# AN_MUX.net
KiCad netlist of a schematic drawn in Altium Designer
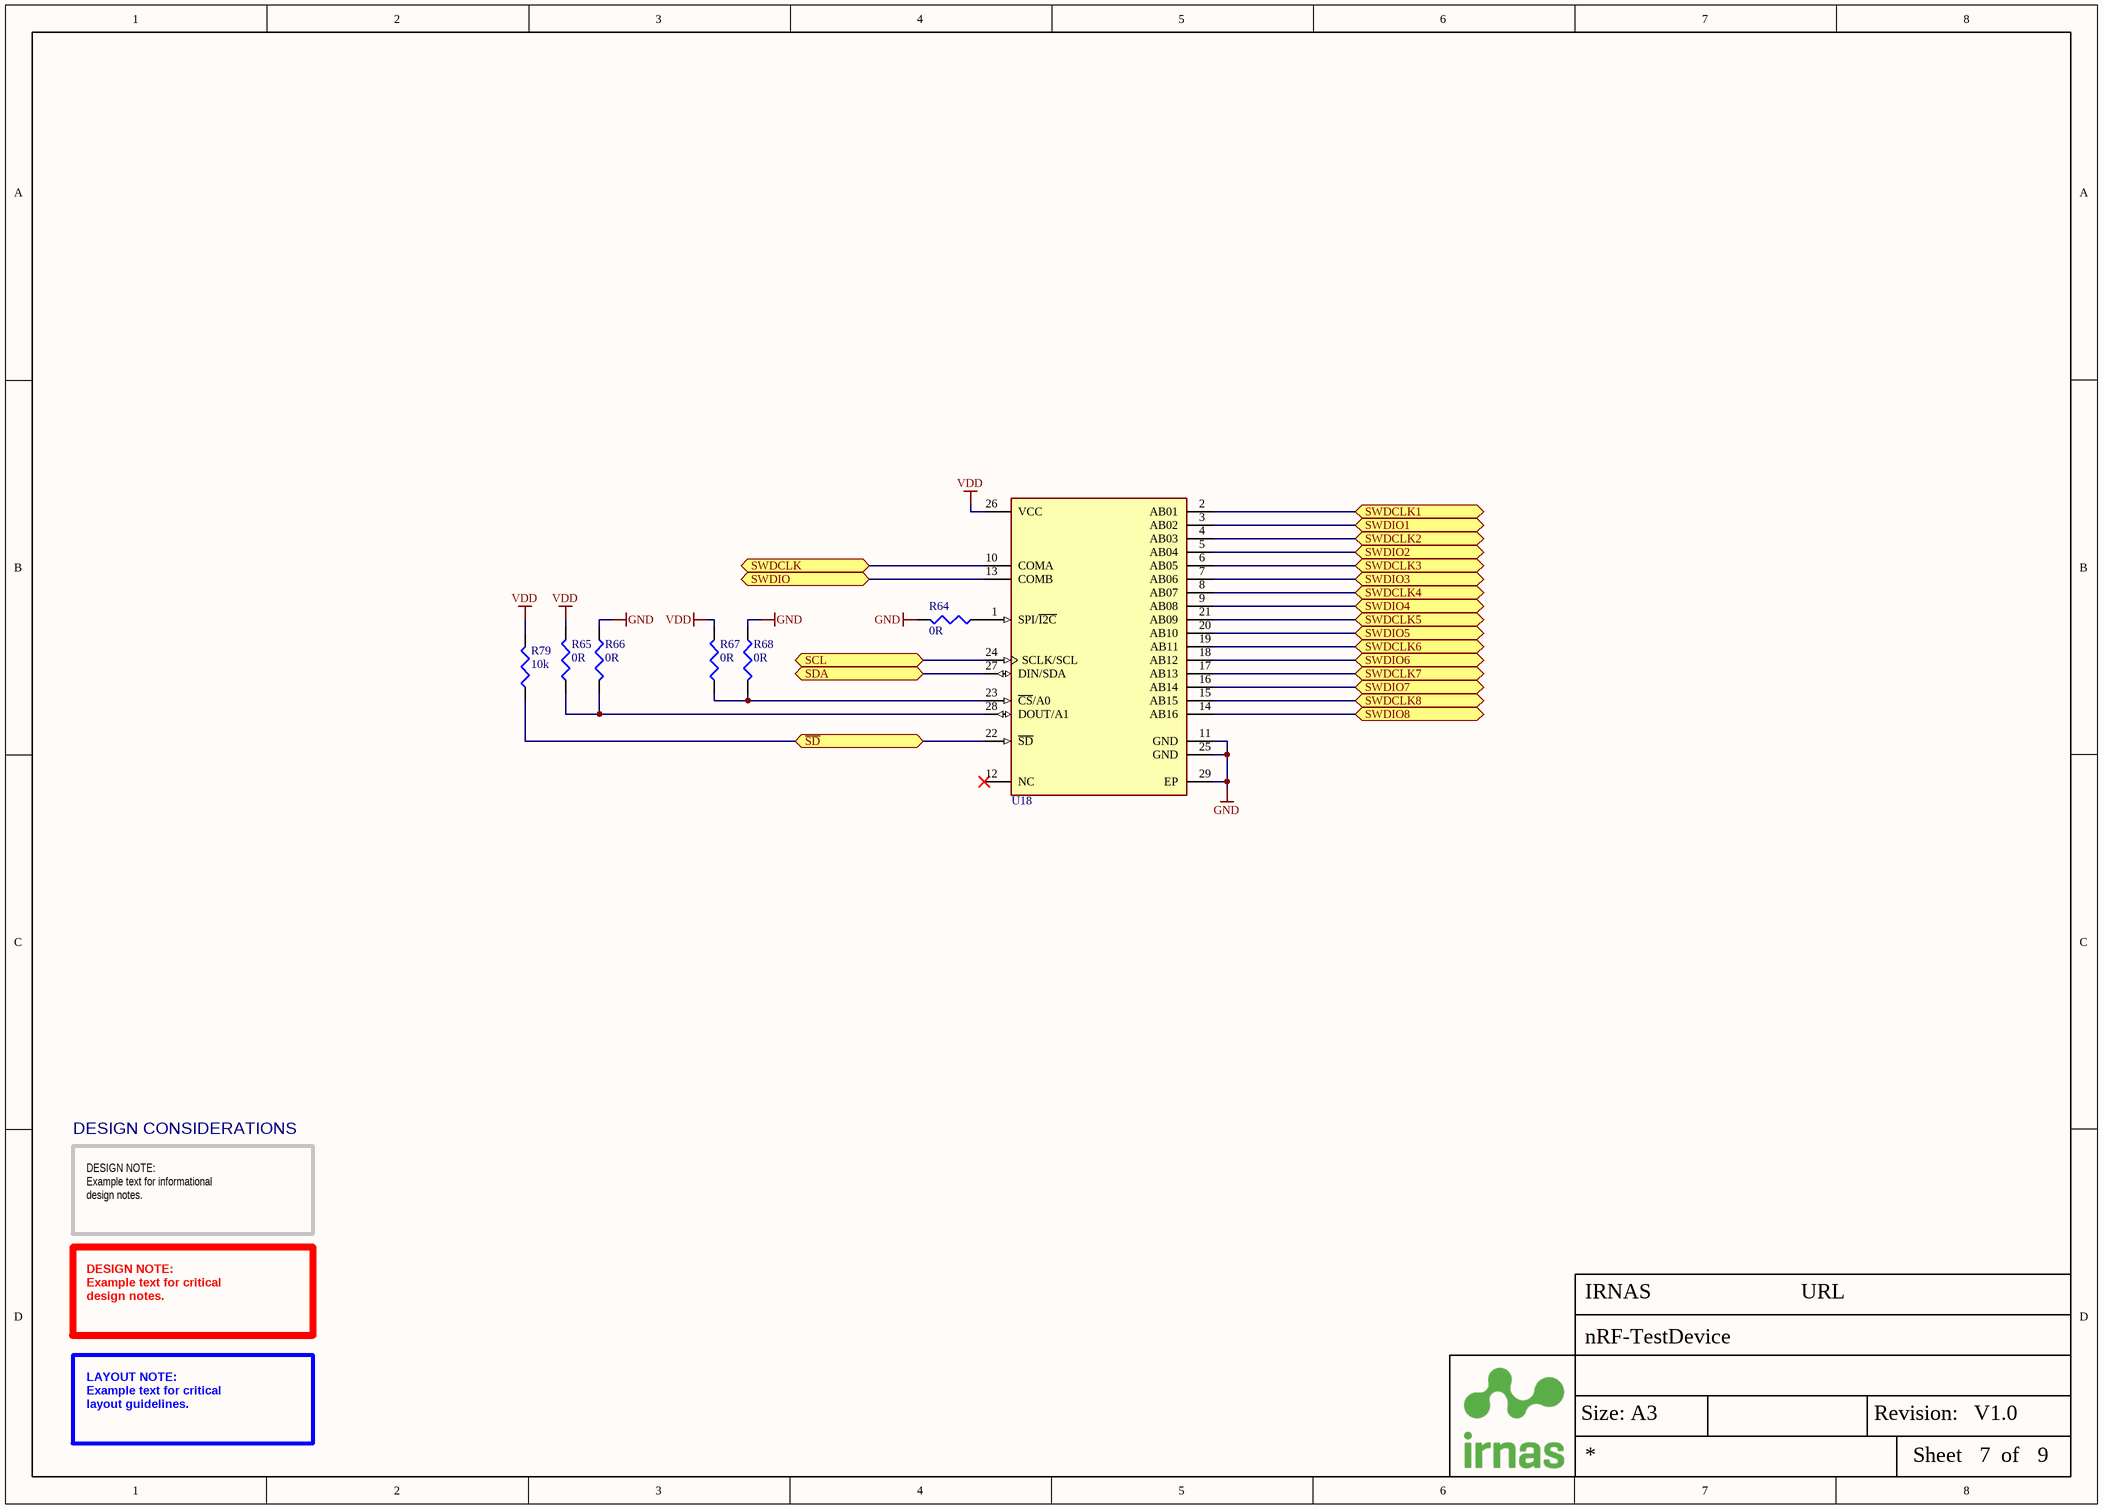
[diagram p0: AN_MUX.SchDoc]

(export (version "E")
  (design (tool "Eeschema 10.0.6"))
  (components
    (comp (ref "R64")
      (value "0R")
      (footprint "RES0402")
      (description "RESISTOR, 0402, 0R, ANTI SULFURATION")
      (fields
        (field (name "MANUFACTURER") "Multicomp")
        (field (name "MANUFACTURER PART NUMBER") "MCMR04X000PTL")
      )
      (libsource (lib "Passive") (part "R - 0R/0402"))
    )
    (comp (ref "R65")
      (value "0R")
      (footprint "RES0402")
      (description "RESISTOR, 0402, 0R, ANTI SULFURATION")
      (fields
        (field (name "MANUFACTURER") "Multicomp")
        (field (name "MANUFACTURER PART NUMBER") "MCMR04X000PTL")
      )
      (libsource (lib "Passive") (part "R - 0R/0402"))
    )
    (comp (ref "R66")
      (value "0R")
      (footprint "RES0402")
      (description "RESISTOR, 0402, 0R, ANTI SULFURATION")
      (fields
        (field (name "MANUFACTURER") "Multicomp")
        (field (name "MANUFACTURER PART NUMBER") "MCMR04X000PTL")
      )
      (libsource (lib "Passive") (part "R - 0R/0402"))
    )
    (comp (ref "R67")
      (value "0R")
      (footprint "RES0402")
      (description "RESISTOR, 0402, 0R, ANTI SULFURATION")
      (fields
        (field (name "MANUFACTURER") "Multicomp")
        (field (name "MANUFACTURER PART NUMBER") "MCMR04X000PTL")
      )
      (libsource (lib "Passive") (part "R - 0R/0402"))
    )
    (comp (ref "R68")
      (value "0R")
      (footprint "RES0402")
      (description "RESISTOR, 0402, 0R, ANTI SULFURATION")
      (fields
        (field (name "MANUFACTURER") "Multicomp")
        (field (name "MANUFACTURER PART NUMBER") "MCMR04X000PTL")
      )
      (libsource (lib "Passive") (part "R - 0R/0402"))
    )
    (comp (ref "R79")
      (value "10k")
      (footprint "RES0402")
      (fields
        (field (name "MANUFACTURER") "Multicomp")
        (field (name "MANUFACTURER PART NUMBER") "MCWR04X1002FTL")
        (field (name "TOLERANCE") "1%")
      )
      (libsource (lib "Passive") (part "R - 10k/0402"))
    )
    (comp (ref "U18")
      (value "INT - MAX14661ETI+")
      (footprint "Maxim_Integrated_T2844-1_IPC_A")
      (libsource (lib "Active") (part "INT - MAX14661ETI+"))
    )
  )
  (nets
    (net (code "1") (name "/SCL") (class "Default")
      (node (ref "U18") (pin "24") (pinfunction "SCLK/SCL_24") (pintype "input"))
    )
    (net (code "2") (name "/SDA") (class "Default")
      (node (ref "U18") (pin "27") (pinfunction "DIN/SDA_27") (pintype "bidirectional"))
    )
    (net (code "3") (name "/SWDCLK") (class "Default")
      (node (ref "U18") (pin "10") (pinfunction "COMA_10") (pintype "passive"))
    )
    (net (code "4") (name "/SWDCLK1") (class "Default")
      (node (ref "U18") (pin "2") (pinfunction "AB01_2") (pintype "passive"))
    )
    (net (code "5") (name "/SWDCLK2") (class "Default")
      (node (ref "U18") (pin "4") (pinfunction "AB03_4") (pintype "passive"))
    )
    (net (code "6") (name "/SWDCLK3") (class "Default")
      (node (ref "U18") (pin "6") (pinfunction "AB05_6") (pintype "passive"))
    )
    (net (code "7") (name "/SWDCLK4") (class "Default")
      (node (ref "U18") (pin "8") (pinfunction "AB07_8") (pintype "passive"))
    )
    (net (code "8") (name "/SWDCLK5") (class "Default")
      (node (ref "U18") (pin "21") (pinfunction "AB09_21") (pintype "passive"))
    )
    (net (code "9") (name "/SWDCLK6") (class "Default")
      (node (ref "U18") (pin "19") (pinfunction "AB11_19") (pintype "passive"))
    )
    (net (code "10") (name "/SWDCLK7") (class "Default")
      (node (ref "U18") (pin "17") (pinfunction "AB13_17") (pintype "passive"))
    )
    (net (code "11") (name "/SWDCLK8") (class "Default")
      (node (ref "U18") (pin "15") (pinfunction "AB15_15") (pintype "passive"))
    )
    (net (code "12") (name "/SWDIO") (class "Default")
      (node (ref "U18") (pin "13") (pinfunction "COMB_13") (pintype "passive"))
    )
    (net (code "13") (name "/SWDIO1") (class "Default")
      (node (ref "U18") (pin "3") (pinfunction "AB02_3") (pintype "passive"))
    )
    (net (code "14") (name "/SWDIO2") (class "Default")
      (node (ref "U18") (pin "5") (pinfunction "AB04_5") (pintype "passive"))
    )
    (net (code "15") (name "/SWDIO3") (class "Default")
      (node (ref "U18") (pin "7") (pinfunction "AB06_7") (pintype "passive"))
    )
    (net (code "16") (name "/SWDIO4") (class "Default")
      (node (ref "U18") (pin "9") (pinfunction "AB08_9") (pintype "passive"))
    )
    (net (code "17") (name "/SWDIO5") (class "Default")
      (node (ref "U18") (pin "20") (pinfunction "AB10_20") (pintype "passive"))
    )
    (net (code "18") (name "/SWDIO6") (class "Default")
      (node (ref "U18") (pin "18") (pinfunction "AB12_18") (pintype "passive"))
    )
    (net (code "19") (name "/SWDIO7") (class "Default")
      (node (ref "U18") (pin "16") (pinfunction "AB14_16") (pintype "passive"))
    )
    (net (code "20") (name "/SWDIO8") (class "Default")
      (node (ref "U18") (pin "14") (pinfunction "AB16_14") (pintype "passive"))
    )
    (net (code "21") (name "/~{SD}") (class "Default")
      (node (ref "R79") (pin "1") (pinfunction "1_1") (pintype "passive"))
      (node (ref "U18") (pin "22") (pinfunction "~{SD}_22") (pintype "input"))
    )
    (net (code "22") (name "GND") (class "Default")
      (node (ref "R64") (pin "2") (pinfunction "2_2") (pintype "passive"))
      (node (ref "R66") (pin "1") (pinfunction "1_1") (pintype "passive"))
      (node (ref "R68") (pin "1") (pinfunction "1_1") (pintype "passive"))
      (node (ref "U18") (pin "11") (pinfunction "GND_11") (pintype "passive"))
      (node (ref "U18") (pin "25") (pinfunction "GND_25") (pintype "passive"))
      (node (ref "U18") (pin "29") (pinfunction "EP_29") (pintype "passive"))
    )
    (net (code "23") (name "Net-(U18-DOUT{slash}A1)") (class "Default")
      (node (ref "R65") (pin "1") (pinfunction "1_1") (pintype "passive"))
      (node (ref "R66") (pin "2") (pinfunction "2_2") (pintype "passive"))
      (node (ref "U18") (pin "28") (pinfunction "DOUT/A1_28") (pintype "bidirectional"))
    )
    (net (code "24") (name "Net-(U18-SPI{slash}~{I2C})") (class "Default")
      (node (ref "R64") (pin "1") (pinfunction "1_1") (pintype "passive"))
      (node (ref "U18") (pin "1") (pinfunction "SPI/~{I2C}_1") (pintype "input"))
    )
    (net (code "25") (name "Net-(U18-~{CS}{slash}A0)") (class "Default")
      (node (ref "R67") (pin "1") (pinfunction "1_1") (pintype "passive"))
      (node (ref "R68") (pin "2") (pinfunction "2_2") (pintype "passive"))
      (node (ref "U18") (pin "23") (pinfunction "~{CS}/A0_23") (pintype "input"))
    )
    (net (code "26") (name "VDD") (class "Default")
      (node (ref "R65") (pin "2") (pinfunction "2_2") (pintype "passive"))
      (node (ref "R67") (pin "2") (pinfunction "2_2") (pintype "passive"))
      (node (ref "R79") (pin "2") (pinfunction "2_2") (pintype "passive"))
      (node (ref "U18") (pin "26") (pinfunction "VCC_26") (pintype "power_in"))
    )
    (net (code "27") (name "unconnected-(U18-NC-Pad12)") (class "Default")
      (node (ref "U18") (pin "12") (pinfunction "NC_12") (pintype "passive+no_connect"))
    )
  )
)
